# LUCRARE_LICENTA.net
KiCad netlist of a schematic drawn in Altium Designer
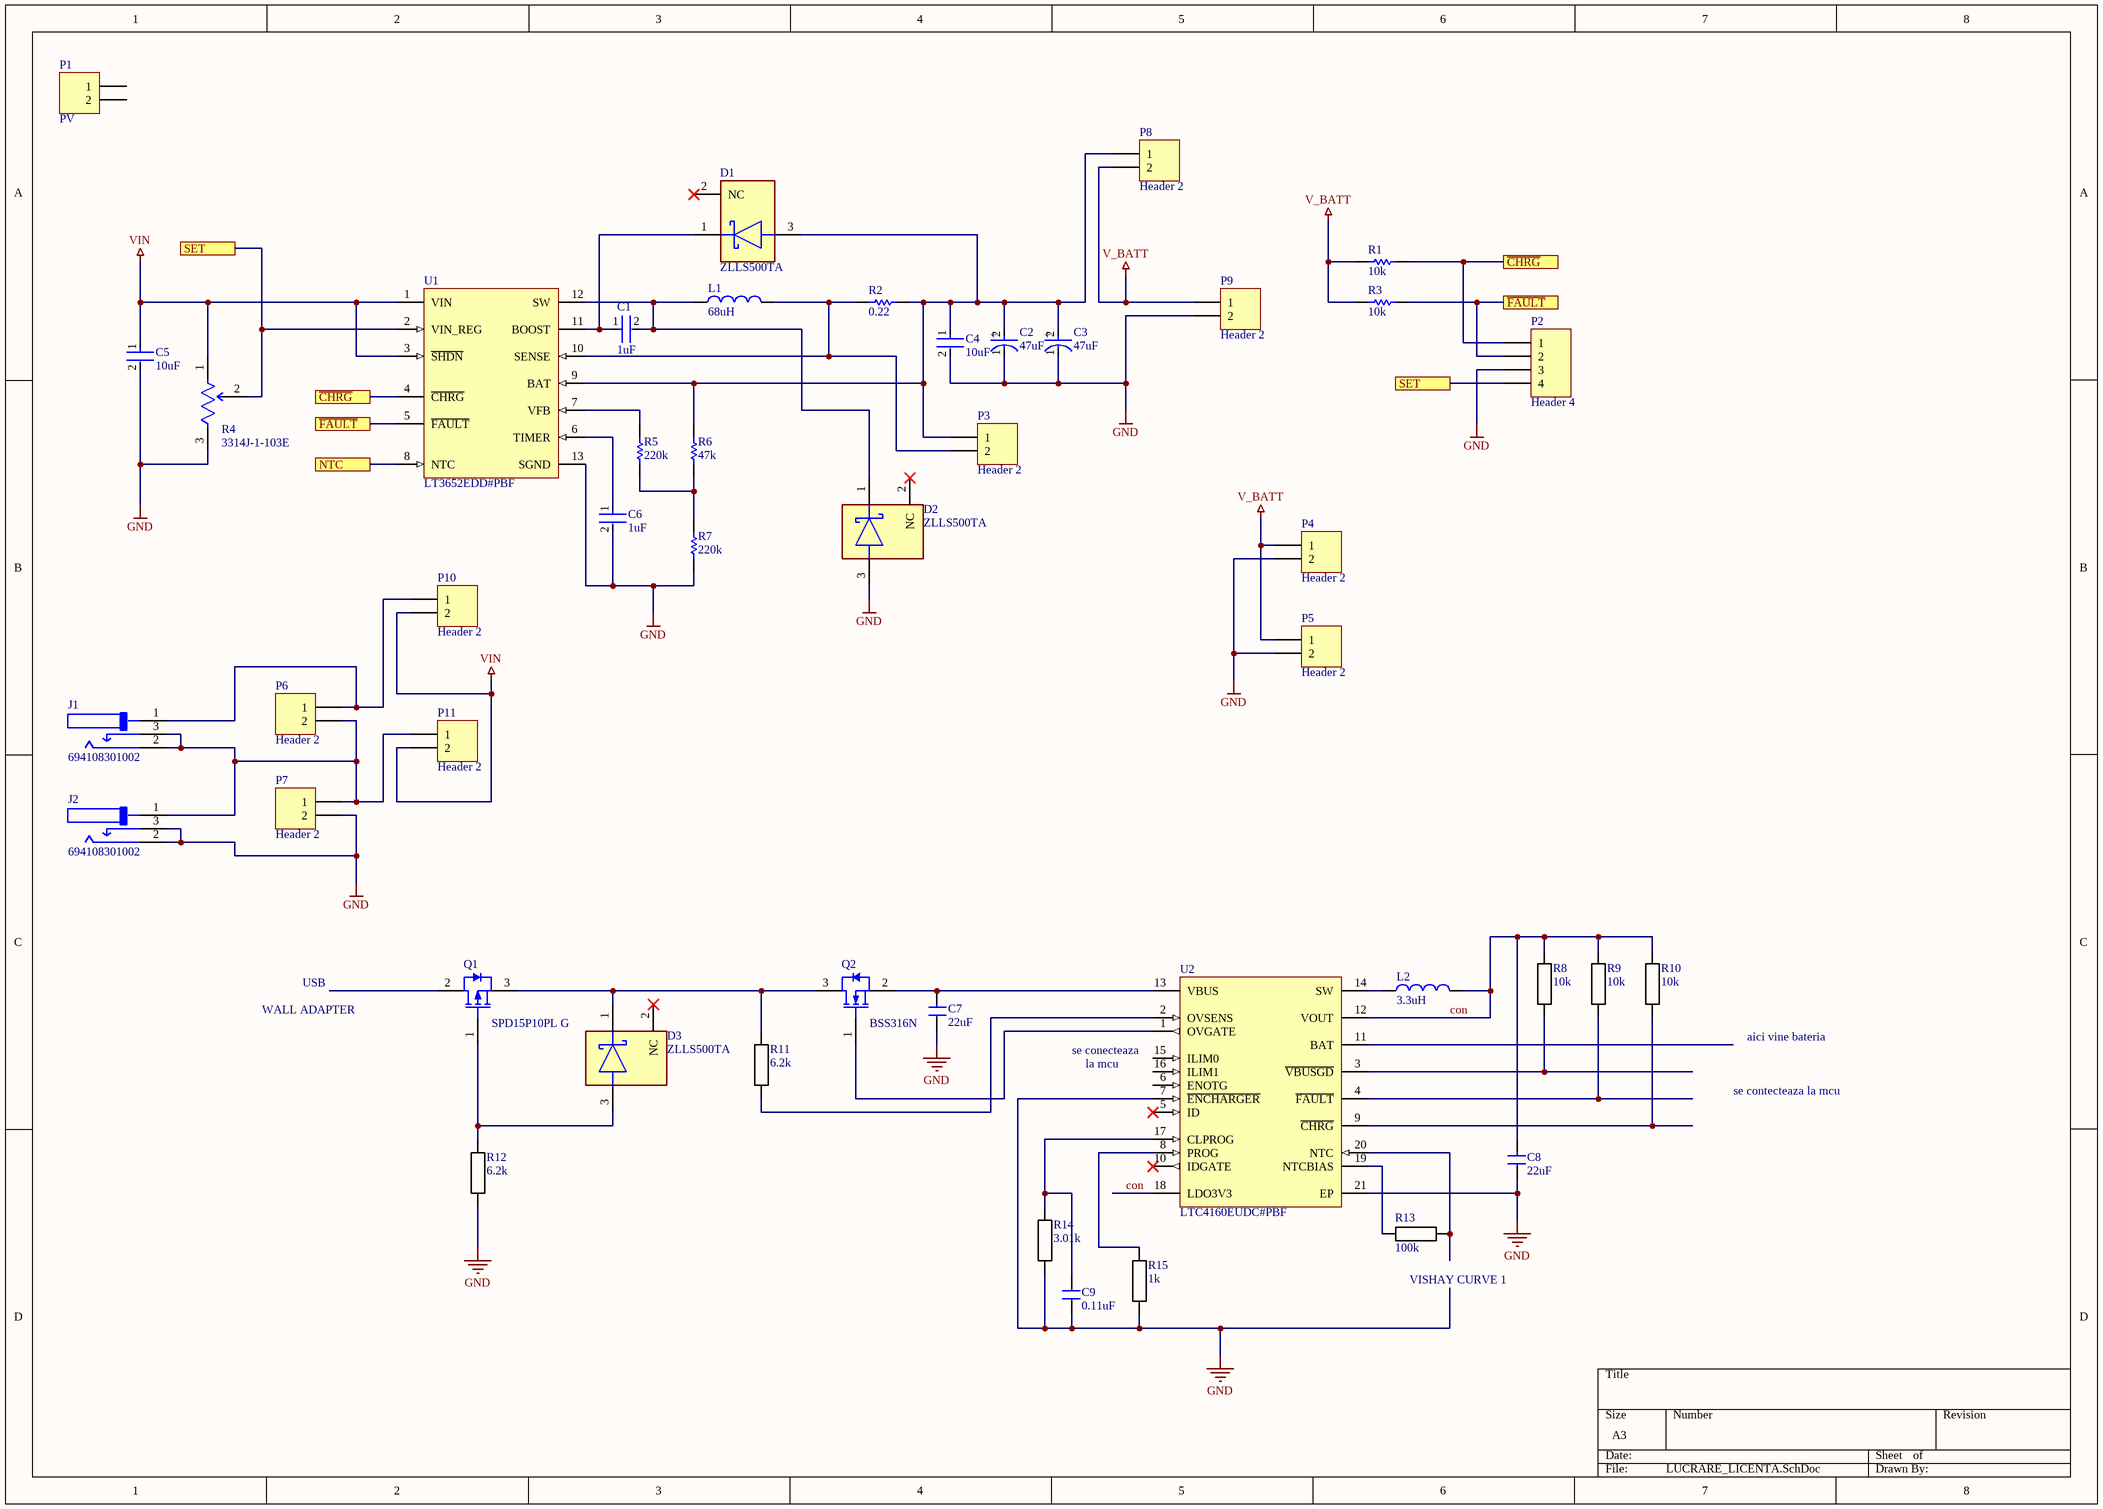
[diagram p0: LUCRARE_LICENTA.SchDoc]

(export (version "E")
  (design (tool "Eeschema 10.0.6"))
  (components
    (comp (ref "C1")
      (value "1uF")
      (footprint "FP-0603-L_1_6_0_15-W_0_8-IPC_C")
      (description "Ceramic Capacitor General Use 1uF ±10% 50V X7R 0603")
      (fields (field (name "TOLERANCE") "10%"))
      (libsource (lib "Altium Content Vault") (part "11868f565c42a9108669ba33697ecf6"))
    )
    (comp (ref "C2")
      (value "47uF")
      (footprint "FP-T491A476M006AT-MFG")
      (description "CAP TANT 47UF 20% 6.3V 1206")
      (fields (field (name "VOLTAGE") "6.3V") (field (name "TOLERANCE") "20%"))
      (libsource (lib "Altium Content Vault") (part "203bc49f2ac43e59fd269a8c329ed05"))
    )
    (comp (ref "C3")
      (value "47uF")
      (footprint "FP-T491A476M006AT-MFG")
      (description "CAP TANT 47UF 20% 6.3V 1206")
      (fields (field (name "VOLTAGE") "6.3V") (field (name "TOLERANCE") "20%"))
      (libsource (lib "Altium Content Vault") (part "203bc49f2ac43e59fd269a8c329ed05"))
    )
    (comp (ref "C4")
      (value "10uF")
      (footprint "FP-0603-L_1_6_0_15-W_0_8-MFG")
      (description "None")
      (fields (field (name "TOLERANCE") "20%") (field (name "VOLTAGE") "6.3V"))
      (libsource (lib "Altium Content Vault") (part "11868f565c42a9108669ba33697ecf6"))
    )
    (comp (ref "C5")
      (value "10uF")
      (footprint "FP-0603-L_1_6_0_15-W_0_8-MFG")
      (description "None")
      (fields (field (name "TOLERANCE") "20%") (field (name "VOLTAGE") "6.3V"))
      (libsource (lib "Altium Content Vault") (part "11868f565c42a9108669ba33697ecf6"))
    )
    (comp (ref "C6")
      (value "1uF")
      (footprint "FP-0603-L_1_6_0_15-W_0_8-IPC_C")
      (description "Ceramic Capacitor General Use 1uF ±10% 50V X7R 0603")
      (fields (field (name "TOLERANCE") "10%"))
      (libsource (lib "Altium Content Vault") (part "11868f565c42a9108669ba33697ecf6"))
    )
    (comp (ref "C7") (value "22uF") (libsource (lib "LUCRARE_LICENTA_SCHEMATIC") (part "CAP 22uF")))
    (comp (ref "C8") (value "22uF") (libsource (lib "LUCRARE_LICENTA_SCHEMATIC") (part "CAP 22uF")))
    (comp (ref "C9") (value "0.11uF") (libsource (lib "LUCRARE_LICENTA_SCHEMATIC") (part "CAP 0.1uF")))
    (comp (ref "D1")
      (value "ZLLS500TA")
      (footprint "FP-SOT23-IPC_B")
      (description "DIODE SCHOTTKY 40V 700MA SOT23-3")
      (libsource (lib "") (part "b02bf5cfd78647b0d44792585de17e4_1"))
    )
    (comp (ref "D2")
      (value "ZLLS500TA")
      (footprint "FP-SOT23-IPC_B")
      (description "DIODE SCHOTTKY 40V 700MA SOT23-3")
      (libsource (lib "Altium Content Vault") (part "b02bf5cfd78647b0d44792585de17e4"))
    )
    (comp (ref "D3")
      (value "ZLLS500TA")
      (footprint "FP-SOT23-IPC_B")
      (description "DIODE SCHOTTKY 40V 700MA SOT23-3")
      (libsource (lib "Altium Content Vault") (part "b02bf5cfd78647b0d44792585de17e4"))
    )
    (comp (ref "J1")
      (value "694108301002")
      (footprint "FP-694108301002-MFG")
      (description "CONN PWR JACK 2.5X5.5MM SOLDER")
      (libsource (lib "Altium Content Vault") (part "cd60c875d5498b43a84108135f4e725"))
    )
    (comp (ref "J2")
      (value "694108301002")
      (footprint "FP-694108301002-MFG")
      (description "CONN PWR JACK 2.5X5.5MM SOLDER")
      (libsource (lib "Altium Content Vault") (part "cd60c875d5498b43a84108135f4e725"))
    )
    (comp (ref "L1") (value "68uH") (libsource (lib "LUCRARE_LICENTA_SCHEMATIC") (part "INDUCTOR 68uH")))
    (comp (ref "L2") (value "3.3uH") (libsource (lib "LUCRARE_LICENTA_SCHEMATIC") (part "INDUCTOR 3.3uH")))
    (comp (ref "P1")
      (value "PV")
      (footprint "HDR1X2")
      (description "Header, 2-Pin")
      (fields (field (name "PUBLISHER") "Altium Limited"))
      (libsource (lib "") (part "Header 2_1"))
    )
    (comp (ref "P2")
      (value "Header 4")
      (footprint "HDR1X4")
      (description "Header, 4-Pin")
      (fields (field (name "PUBLISHER") "Altium Limited"))
      (libsource (lib "Miscellaneous Connectors") (part "Header 4"))
    )
    (comp (ref "P3")
      (value "Header 2")
      (footprint "HDR1X2")
      (description "Header, 2-Pin")
      (fields (field (name "PUBLISHER") "Altium Limited"))
      (libsource (lib "Miscellaneous Connectors") (part "Header 2"))
    )
    (comp (ref "P4")
      (value "Header 2")
      (footprint "HDR1X2")
      (description "Header, 2-Pin")
      (fields (field (name "PUBLISHER") "Altium Limited"))
      (libsource (lib "Miscellaneous Connectors") (part "Header 2"))
    )
    (comp (ref "P5")
      (value "Header 2")
      (footprint "HDR1X2")
      (description "Header, 2-Pin")
      (fields (field (name "PUBLISHER") "Altium Limited"))
      (libsource (lib "Miscellaneous Connectors") (part "Header 2"))
    )
    (comp (ref "P6")
      (value "Header 2")
      (footprint "HDR1X2")
      (description "Header, 2-Pin")
      (fields (field (name "PUBLISHER") "Altium Limited"))
      (libsource (lib "") (part "Header 2_1"))
    )
    (comp (ref "P7")
      (value "Header 2")
      (footprint "HDR1X2")
      (description "Header, 2-Pin")
      (fields (field (name "PUBLISHER") "Altium Limited"))
      (libsource (lib "") (part "Header 2_1"))
    )
    (comp (ref "P8")
      (value "Header 2")
      (footprint "HDR1X2")
      (description "Header, 2-Pin")
      (fields (field (name "PUBLISHER") "Altium Limited"))
      (libsource (lib "Miscellaneous Connectors") (part "Header 2"))
    )
    (comp (ref "P9")
      (value "Header 2")
      (footprint "HDR1X2")
      (description "Header, 2-Pin")
      (fields (field (name "PUBLISHER") "Altium Limited"))
      (libsource (lib "Miscellaneous Connectors") (part "Header 2"))
    )
    (comp (ref "P10")
      (value "Header 2")
      (footprint "HDR1X2")
      (description "Header, 2-Pin")
      (fields (field (name "PUBLISHER") "Altium Limited"))
      (libsource (lib "Miscellaneous Connectors") (part "Header 2"))
    )
    (comp (ref "P11")
      (value "Header 2")
      (footprint "HDR1X2")
      (description "Header, 2-Pin")
      (fields (field (name "PUBLISHER") "Altium Limited"))
      (libsource (lib "Miscellaneous Connectors") (part "Header 2"))
    )
    (comp (ref "Q1")
      (value "SPD15P10PL G")
      (footprint "INF-PG-TO252-3-1_N")
      (fields (field (name "MANUFACTURER") "Infineon"))
      (libsource (lib "Altium Content Vault") (part "INF-PEMOS-GDS-3"))
    )
    (comp (ref "Q2")
      (value "BSS316N")
      (footprint "INF-PG-SOT23_L")
      (fields (field (name "MANUFACTURER") "Infineon"))
      (libsource (lib "Altium Content Vault") (part "INF-NEMOS-GSD-3"))
    )
    (comp (ref "R1")
      (value "10k")
      (footprint "RESC1609X55X30LL15T15")
      (description "Chip Resistor, 10 KOhm, +/- 1%, 0.1 W, -55 to 155 degC, 0603 (1608 Metric), RoHS, Tape and Reel")
      (fields (field (name "TOLERANCE") "1%") (field (name "MANUFACTURER") "Panasonic"))
      (libsource (lib "Altium Content Vault") (part "RES-2"))
    )
    (comp (ref "R2")
      (value "0.22")
      (footprint "RESC1608X55X30NL15T15")
      (fields (field (name "PART NUMBER") "ERJ-3RQFR22V") (field (name "MANUFACTURER") "Panasonic"))
      (libsource (lib "Altium Content Vault") (part "RES"))
    )
    (comp (ref "R3")
      (value "10k")
      (footprint "RESC1609X55X30LL15T15")
      (description "Chip Resistor, 10 KOhm, +/- 1%, 0.1 W, -55 to 155 degC, 0603 (1608 Metric), RoHS, Tape and Reel")
      (fields (field (name "TOLERANCE") "1%") (field (name "MANUFACTURER") "Panasonic"))
      (libsource (lib "Altium Content Vault") (part "RES-2"))
    )
    (comp (ref "R4")
      (value "3314J-1-103E")
      (footprint "FP-3314J-1-MFG")
      (description "TRIMMER 10K OHM 0.25W J LEAD TOP")
      (libsource (lib "Altium Content Vault") (part "13357d81287629c2fd191d242cfa50c"))
    )
    (comp (ref "R5")
      (value "220k")
      (footprint "RESC1608X55X25ML10T15")
      (description "Chip Resistor, 220 KOhm, +/- 1%, 100 mW, -55 to 155 degC, 0603 (1608 Metric), RoHS, Tape and Reel")
      (libsource (lib "Altium Content Vault") (part "RES-2"))
    )
    (comp (ref "R6")
      (value "47k")
      (footprint "RESC1608X55X30NL15T15")
      (description "Chip Resistor, 47 KOhm, +/- 1%, 0.1 W, -55 to 155 degC, 0603 (1608 Metric), RoHS, Tape and Reel")
      (libsource (lib "Altium Content Vault") (part "RES-2"))
    )
    (comp (ref "R7")
      (value "220k")
      (footprint "RESC1608X55X25ML10T15")
      (description "Chip Resistor, 220 KOhm, +/- 1%, 100 mW, -55 to 155 degC, 0603 (1608 Metric), RoHS, Tape and Reel")
      (libsource (lib "Altium Content Vault") (part "RES-2"))
    )
    (comp (ref "R8") (value "10k") (libsource (lib "LUCRARE_LICENTA_SCHEMATIC") (part "RS 10k")))
    (comp (ref "R9") (value "10k") (libsource (lib "LUCRARE_LICENTA_SCHEMATIC") (part "RS 10k")))
    (comp (ref "R10") (value "10k") (libsource (lib "LUCRARE_LICENTA_SCHEMATIC") (part "RS 10k")))
    (comp (ref "R11") (value "6.2k") (libsource (lib "LUCRARE_LICENTA_SCHEMATIC") (part "RS 6.2k")))
    (comp (ref "R12") (value "6.2k") (libsource (lib "LUCRARE_LICENTA_SCHEMATIC") (part "RS 6.2k")))
    (comp (ref "R13") (value "100k") (libsource (lib "LUCRARE_LICENTA_SCHEMATIC") (part "RS 100k")))
    (comp (ref "R14") (value "3.01k") (libsource (lib "LUCRARE_LICENTA_SCHEMATIC") (part "RS 3.01k")))
    (comp (ref "R15") (value "1k") (libsource (lib "LUCRARE_LICENTA_SCHEMATIC") (part "RS 1k")))
    (comp (ref "U1")
      (value "LT3652EDD#PBF")
      (footprint "LT-DD-12_V")
      (description "Power Tracking 2 A Battery Charger for Solar Power, 12-pin SON (DD-12), -40 to 125 degC, Pb-Free")
      (fields (field (name "MANUFACTURER") "Linear Technology"))
      (libsource (lib "Altium Content Vault") (part "LT-LT3652XX-12"))
    )
    (comp (ref "U2")
      (value "LTC4160EUDC#PBF")
      (footprint "LT-UDC-20_N")
      (fields (field (name "MANUFACTURER") "Linear Technology"))
      (libsource (lib "Altium Content Vault") (part "LT-LTC4160-UDC-20"))
    )
  )
  (nets
    (net (code "1") (name "/NTC") (class "Default")
      (node (ref "U1") (pin "8") (pinfunction "NTC_8") (pintype "input"))
    )
    (net (code "2") (name "/SET") (class "Default")
      (node (ref "P2") (pin "4") (pinfunction "4_4") (pintype "passive"))
      (node (ref "R4") (pin "2") (pinfunction "WIPER_2") (pintype "passive"))
      (node (ref "U1") (pin "2") (pinfunction "VIN_REG_2") (pintype "input"))
    )
    (net (code "3") (name "/con") (class "Default")
      (node (ref "C8") (pin "2") (pinfunction "2_2") (pintype "passive"))
      (node (ref "L2") (pin "2") (pinfunction "2_2") (pintype "passive"))
      (node (ref "R10") (pin "21") (pinfunction "21_21") (pintype "passive"))
      (node (ref "R8") (pin "21") (pinfunction "21_21") (pintype "passive"))
      (node (ref "R9") (pin "21") (pinfunction "21_21") (pintype "passive"))
      (node (ref "U2") (pin "12") (pinfunction "VOUT_12") (pintype "power_in"))
      (node (ref "U2") (pin "18") (pinfunction "LDO3V3_18") (pintype "power_in"))
    )
    (net (code "4") (name "/~{CHRG}") (class "Default")
      (node (ref "P2") (pin "1") (pinfunction "1_1") (pintype "passive"))
      (node (ref "R1") (pin "2") (pinfunction "2_2") (pintype "passive"))
      (node (ref "U1") (pin "4") (pinfunction "~{CHRG}_4") (pintype "tri_state"))
    )
    (net (code "5") (name "/~{FAULT}") (class "Default")
      (node (ref "P2") (pin "2") (pinfunction "2_2") (pintype "passive"))
      (node (ref "R3") (pin "2") (pinfunction "2_2") (pintype "passive"))
      (node (ref "U1") (pin "5") (pinfunction "~{FAULT}_5") (pintype "tri_state"))
    )
    (net (code "6") (name "GND") (class "Default")
      (node (ref "C2") (pin "1") (pinfunction "C_1") (pintype "passive"))
      (node (ref "C3") (pin "1") (pinfunction "C_1") (pintype "passive"))
      (node (ref "C4") (pin "2") (pinfunction "2_2") (pintype "passive"))
      (node (ref "C5") (pin "2") (pinfunction "2_2") (pintype "passive"))
      (node (ref "C6") (pin "2") (pinfunction "2_2") (pintype "passive"))
      (node (ref "C7") (pin "2") (pinfunction "2_2") (pintype "passive"))
      (node (ref "C8") (pin "1") (pinfunction "1_1") (pintype "passive"))
      (node (ref "C9") (pin "1") (pinfunction "1_1") (pintype "passive"))
      (node (ref "D2") (pin "3") (pinfunction "A_3") (pintype "passive"))
      (node (ref "J2") (pin "2") (pinfunction "2_2") (pintype "passive"))
      (node (ref "J2") (pin "3") (pinfunction "3_3") (pintype "passive"))
      (node (ref "P2") (pin "3") (pinfunction "3_3") (pintype "passive"))
      (node (ref "P4") (pin "2") (pinfunction "2_2") (pintype "passive"))
      (node (ref "P5") (pin "2") (pinfunction "2_2") (pintype "passive"))
      (node (ref "P7") (pin "2") (pinfunction "2_2") (pintype "passive"))
      (node (ref "P9") (pin "2") (pinfunction "2_2") (pintype "passive"))
      (node (ref "R12") (pin "20") (pinfunction "20_20") (pintype "passive"))
      (node (ref "R14") (pin "20") (pinfunction "20_20") (pintype "passive"))
      (node (ref "R15") (pin "20") (pinfunction "20_20") (pintype "passive"))
      (node (ref "R4") (pin "3") (pinfunction "CW_3") (pintype "passive"))
      (node (ref "R7") (pin "1") (pinfunction "1_1") (pintype "passive"))
      (node (ref "U1") (pin "13") (pinfunction "SGND_13") (pintype "power_in"))
      (node (ref "U2") (pin "21") (pinfunction "EP_21") (pintype "power_in"))
      (node (ref "U2") (pin "7") (pinfunction "~{ENCHARGER}_7") (pintype "input"))
    )
    (net (code "7") (name "Net-(C2-A)") (class "Default")
      (node (ref "C2") (pin "2") (pinfunction "A_2") (pintype "passive"))
      (node (ref "C3") (pin "2") (pinfunction "A_2") (pintype "passive"))
      (node (ref "C4") (pin "1") (pinfunction "1_1") (pintype "passive"))
      (node (ref "D1") (pin "3") (pinfunction "A_3") (pintype "passive"))
      (node (ref "P3") (pin "1") (pinfunction "1_1") (pintype "passive"))
      (node (ref "P8") (pin "1") (pinfunction "1_1") (pintype "passive"))
      (node (ref "R2") (pin "2") (pinfunction "2_2") (pintype "passive"))
      (node (ref "R6") (pin "2") (pinfunction "2_2") (pintype "passive"))
      (node (ref "U1") (pin "9") (pinfunction "BAT_9") (pintype "input"))
    )
    (net (code "8") (name "Net-(D1-C)") (class "Default")
      (node (ref "C1") (pin "1") (pinfunction "1_1") (pintype "passive"))
      (node (ref "D1") (pin "1") (pinfunction "C_1") (pintype "passive"))
      (node (ref "U1") (pin "11") (pinfunction "BOOST_11") (pintype "power_in"))
    )
    (net (code "9") (name "Net-(D2-C)") (class "Default")
      (node (ref "C1") (pin "2") (pinfunction "2_2") (pintype "passive"))
      (node (ref "D2") (pin "1") (pinfunction "C_1") (pintype "passive"))
      (node (ref "L1") (pin "1") (pinfunction "1_1") (pintype "passive"))
      (node (ref "U1") (pin "12") (pinfunction "SW_12") (pintype "power_in"))
    )
    (net (code "10") (name "Net-(D3-A)") (class "Default")
      (node (ref "D3") (pin "3") (pinfunction "A_3") (pintype "passive"))
      (node (ref "Q1") (pin "1") (pinfunction "GATE_1") (pintype "passive"))
      (node (ref "R12") (pin "21") (pinfunction "21_21") (pintype "passive"))
    )
    (net (code "11") (name "Net-(D3-C)") (class "Default")
      (node (ref "D3") (pin "1") (pinfunction "C_1") (pintype "passive"))
      (node (ref "Q1") (pin "3") (pinfunction "SOURCE_3") (pintype "passive"))
      (node (ref "Q2") (pin "3") (pinfunction "DRAIN_3") (pintype "passive"))
      (node (ref "R11") (pin "21") (pinfunction "21_21") (pintype "passive"))
    )
    (net (code "12") (name "Net-(J1-Pad1)") (class "Default")
      (node (ref "J1") (pin "1") (pinfunction "1_1") (pintype "passive"))
      (node (ref "P10") (pin "1") (pinfunction "1_1") (pintype "passive"))
      (node (ref "P6") (pin "1") (pinfunction "1_1") (pintype "passive"))
    )
    (net (code "13") (name "Net-(J1-Pad2)") (class "Default")
      (node (ref "J1") (pin "2") (pinfunction "2_2") (pintype "passive"))
      (node (ref "J1") (pin "3") (pinfunction "3_3") (pintype "passive"))
      (node (ref "J2") (pin "1") (pinfunction "1_1") (pintype "passive"))
      (node (ref "P11") (pin "1") (pinfunction "1_1") (pintype "passive"))
      (node (ref "P6") (pin "2") (pinfunction "2_2") (pintype "passive"))
      (node (ref "P7") (pin "1") (pinfunction "1_1") (pintype "passive"))
    )
    (net (code "14") (name "Net-(Q2-GATE)") (class "Default")
      (node (ref "Q2") (pin "1") (pinfunction "GATE_1") (pintype "passive"))
      (node (ref "U2") (pin "1") (pinfunction "OVGATE_1") (pintype "output"))
    )
    (net (code "15") (name "Net-(Q2-SOURCE)") (class "Default")
      (node (ref "C7") (pin "1") (pinfunction "1_1") (pintype "passive"))
      (node (ref "Q2") (pin "2") (pinfunction "SOURCE_2") (pintype "passive"))
      (node (ref "U2") (pin "13") (pinfunction "VBUS_13") (pintype "power_in"))
    )
    (net (code "16") (name "Net-(R5-Pad1)") (class "Default")
      (node (ref "R5") (pin "1") (pinfunction "1_1") (pintype "passive"))
      (node (ref "R6") (pin "1") (pinfunction "1_1") (pintype "passive"))
      (node (ref "R7") (pin "2") (pinfunction "2_2") (pintype "passive"))
    )
    (net (code "17") (name "Net-(U1-SENSE)") (class "Default")
      (node (ref "L1") (pin "2") (pinfunction "2_2") (pintype "passive"))
      (node (ref "P3") (pin "2") (pinfunction "2_2") (pintype "passive"))
      (node (ref "R2") (pin "1") (pinfunction "1_1") (pintype "passive"))
      (node (ref "U1") (pin "10") (pinfunction "SENSE_10") (pintype "input"))
    )
    (net (code "18") (name "Net-(U1-TIMER)") (class "Default")
      (node (ref "C6") (pin "1") (pinfunction "1_1") (pintype "passive"))
      (node (ref "U1") (pin "6") (pinfunction "TIMER_6") (pintype "input"))
    )
    (net (code "19") (name "Net-(U1-VFB)") (class "Default")
      (node (ref "R5") (pin "2") (pinfunction "2_2") (pintype "passive"))
      (node (ref "U1") (pin "7") (pinfunction "VFB_7") (pintype "input"))
    )
    (net (code "20") (name "Net-(U2-CLPROG)") (class "Default")
      (node (ref "C9") (pin "2") (pinfunction "2_2") (pintype "passive"))
      (node (ref "R14") (pin "21") (pinfunction "21_21") (pintype "passive"))
      (node (ref "U2") (pin "17") (pinfunction "CLPROG_17") (pintype "input"))
    )
    (net (code "21") (name "Net-(U2-NTC)") (class "Default")
      (node (ref "R13") (pin "20") (pinfunction "20_20") (pintype "passive"))
      (node (ref "U2") (pin "20") (pinfunction "NTC_20") (pintype "input"))
    )
    (net (code "22") (name "Net-(U2-NTCBIAS)") (class "Default")
      (node (ref "R13") (pin "21") (pinfunction "21_21") (pintype "passive"))
      (node (ref "U2") (pin "19") (pinfunction "NTCBIAS_19") (pintype "passive"))
    )
    (net (code "23") (name "Net-(U2-OVSENS)") (class "Default")
      (node (ref "R11") (pin "20") (pinfunction "20_20") (pintype "passive"))
      (node (ref "U2") (pin "2") (pinfunction "OVSENS_2") (pintype "input"))
    )
    (net (code "24") (name "Net-(U2-PROG)") (class "Default")
      (node (ref "R15") (pin "21") (pinfunction "21_21") (pintype "passive"))
      (node (ref "U2") (pin "8") (pinfunction "PROG_8") (pintype "input"))
    )
    (net (code "25") (name "Net-(U2-SW)") (class "Default")
      (node (ref "L2") (pin "1") (pinfunction "1_1") (pintype "passive"))
      (node (ref "U2") (pin "14") (pinfunction "SW_14") (pintype "power_in"))
    )
    (net (code "26") (name "Net-(U2-~{CHRG})") (class "Default")
      (node (ref "R10") (pin "20") (pinfunction "20_20") (pintype "passive"))
      (node (ref "U2") (pin "9") (pinfunction "~{CHRG}_9") (pintype "open_collector"))
    )
    (net (code "27") (name "Net-(U2-~{FAULT})") (class "Default")
      (node (ref "R9") (pin "20") (pinfunction "20_20") (pintype "passive"))
      (node (ref "U2") (pin "4") (pinfunction "~{FAULT}_4") (pintype "open_collector"))
    )
    (net (code "28") (name "Net-(U2-~{VBUSGD})") (class "Default")
      (node (ref "R8") (pin "20") (pinfunction "20_20") (pintype "passive"))
      (node (ref "U2") (pin "3") (pinfunction "~{VBUSGD}_3") (pintype "open_collector"))
    )
    (net (code "29") (name "VIN") (class "Default")
      (node (ref "C5") (pin "1") (pinfunction "1_1") (pintype "passive"))
      (node (ref "P10") (pin "2") (pinfunction "2_2") (pintype "passive"))
      (node (ref "P11") (pin "2") (pinfunction "2_2") (pintype "passive"))
      (node (ref "R4") (pin "1") (pinfunction "CCW_1") (pintype "passive"))
      (node (ref "U1") (pin "1") (pinfunction "VIN_1") (pintype "power_in"))
      (node (ref "U1") (pin "3") (pinfunction "~{SHDN}_3") (pintype "input"))
    )
    (net (code "30") (name "V_BATT") (class "Default")
      (node (ref "P4") (pin "1") (pinfunction "1_1") (pintype "passive"))
      (node (ref "P5") (pin "1") (pinfunction "1_1") (pintype "passive"))
      (node (ref "P8") (pin "2") (pinfunction "2_2") (pintype "passive"))
      (node (ref "P9") (pin "1") (pinfunction "1_1") (pintype "passive"))
      (node (ref "R1") (pin "1") (pinfunction "1_1") (pintype "passive"))
      (node (ref "R3") (pin "1") (pinfunction "1_1") (pintype "passive"))
    )
    (net (code "31") (name "unconnected-(D1-NC-Pad2)") (class "Default")
      (node (ref "D1") (pin "2") (pinfunction "NC_2") (pintype "passive+no_connect"))
    )
    (net (code "32") (name "unconnected-(D2-NC-Pad2)") (class "Default")
      (node (ref "D2") (pin "2") (pinfunction "NC_2") (pintype "passive+no_connect"))
    )
    (net (code "33") (name "unconnected-(D3-NC-Pad2)") (class "Default")
      (node (ref "D3") (pin "2") (pinfunction "NC_2") (pintype "passive+no_connect"))
    )
    (net (code "34") (name "unconnected-(P1-Pad1)") (class "Default")
      (node (ref "P1") (pin "1") (pinfunction "1_1") (pintype "passive"))
    )
    (net (code "35") (name "unconnected-(P1-Pad2)") (class "Default")
      (node (ref "P1") (pin "2") (pinfunction "2_2") (pintype "passive"))
    )
    (net (code "36") (name "unconnected-(Q1-DRAIN-Pad2)") (class "Default")
      (node (ref "Q1") (pin "2") (pinfunction "DRAIN_2") (pintype "passive"))
    )
    (net (code "37") (name "unconnected-(U2-BAT-Pad11)") (class "Default")
      (node (ref "U2") (pin "11") (pinfunction "BAT_11") (pintype "power_in"))
    )
    (net (code "38") (name "unconnected-(U2-ENOTG-Pad6)") (class "Default")
      (node (ref "U2") (pin "6") (pinfunction "ENOTG_6") (pintype "input"))
    )
    (net (code "39") (name "unconnected-(U2-ID-Pad5)") (class "Default")
      (node (ref "U2") (pin "5") (pinfunction "ID_5") (pintype "input+no_connect"))
    )
    (net (code "40") (name "unconnected-(U2-IDGATE-Pad10)") (class "Default")
      (node (ref "U2") (pin "10") (pinfunction "IDGATE_10") (pintype "output+no_connect"))
    )
    (net (code "41") (name "unconnected-(U2-ILIM0-Pad15)") (class "Default")
      (node (ref "U2") (pin "15") (pinfunction "ILIM0_15") (pintype "input"))
    )
    (net (code "42") (name "unconnected-(U2-ILIM1-Pad16)") (class "Default")
      (node (ref "U2") (pin "16") (pinfunction "ILIM1_16") (pintype "input"))
    )
  )
)
